# DeadOn_RTC_-_DS3234_Breakout-v11.net
KiCad netlist of a schematic drawn in EAGLE
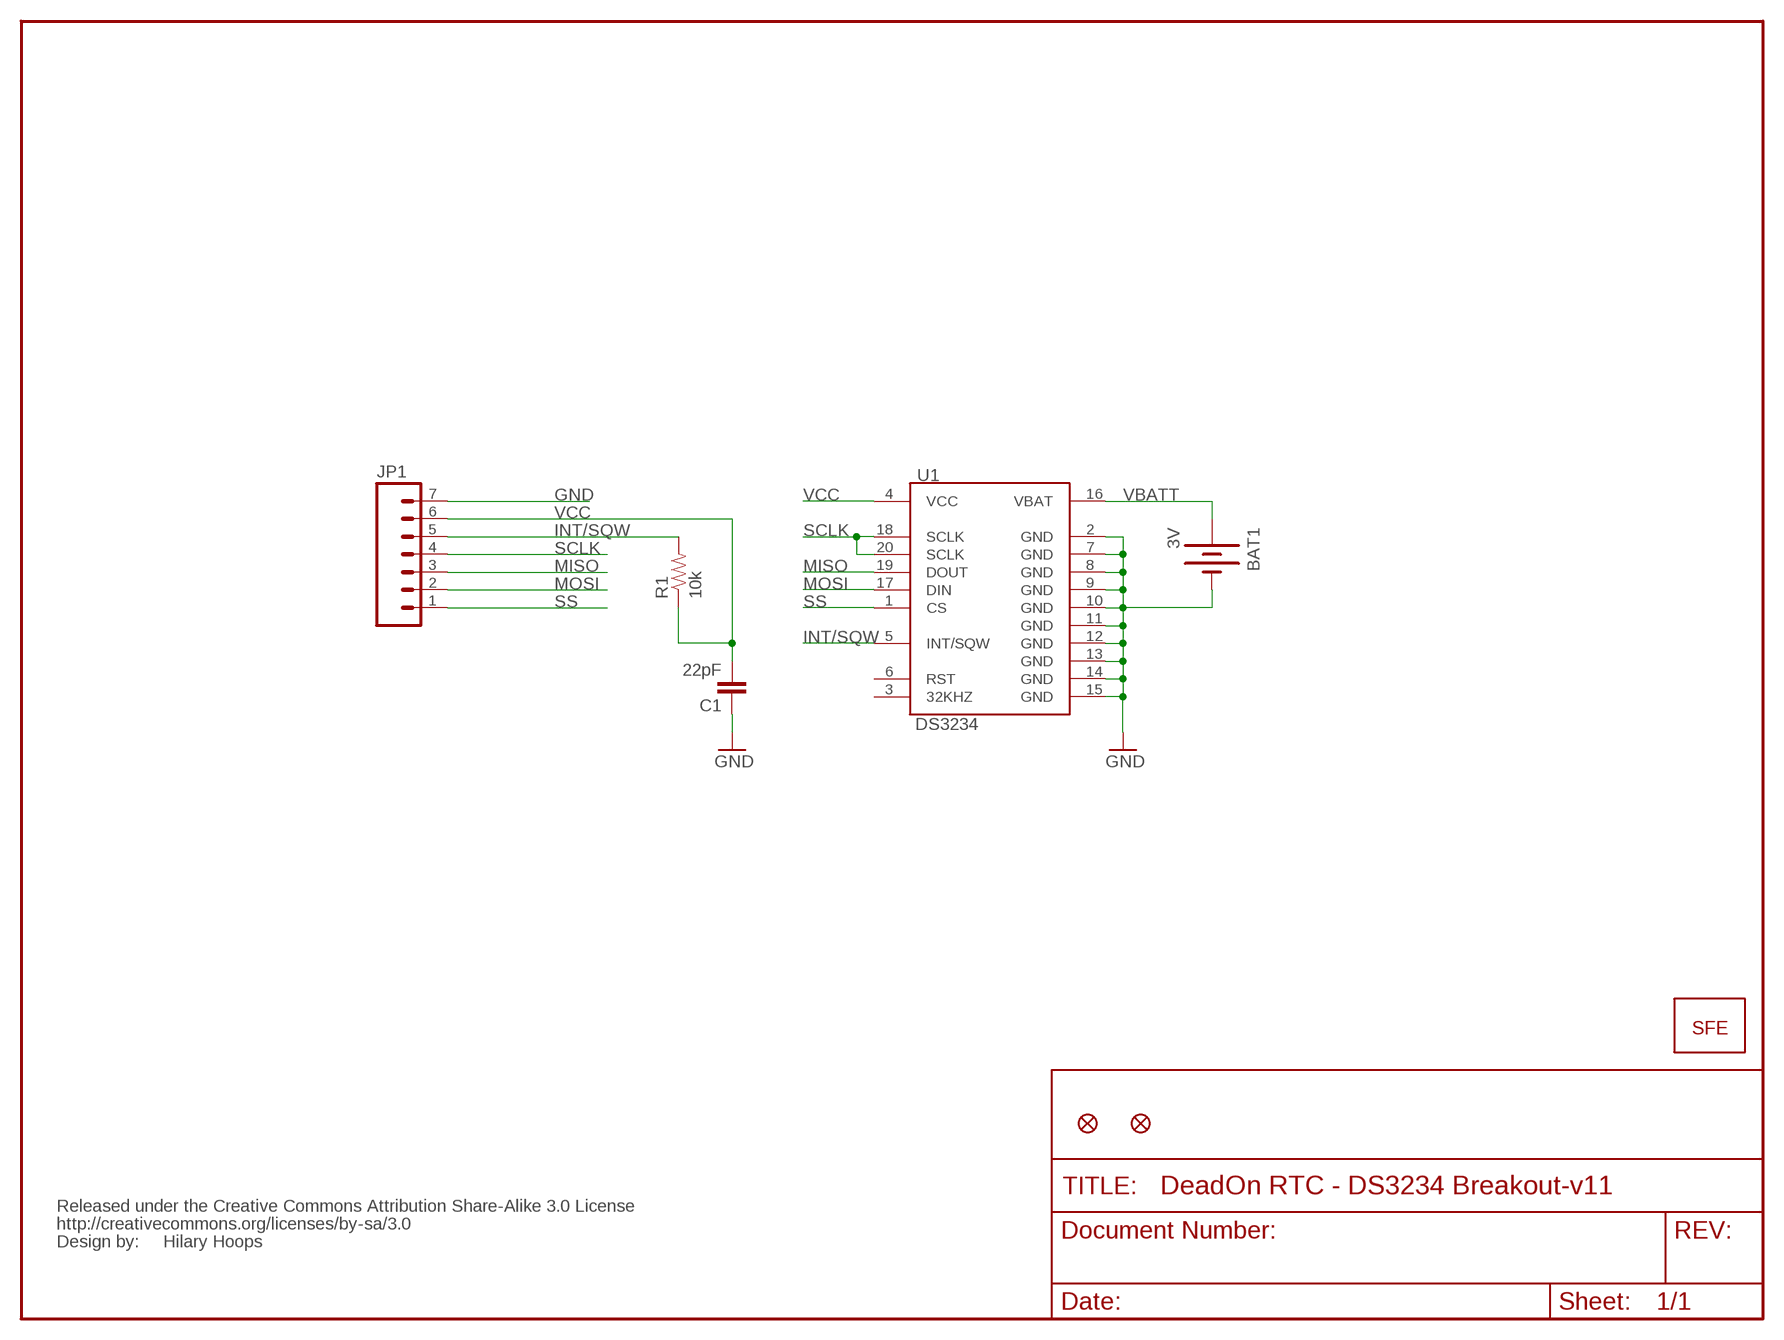
[diagram p0: schematic, sheet 1]

(export (version "E")
  (design (tool "Eeschema 10.0.6"))
  (components
    (comp (ref "BAT1")
      (value "3V")
      (footprint "eagle-import:BATTCON_12MM_CURVED")
      (libsource (lib "eagle-import") (part "BATTERY"))
    )
    (comp (ref "C1")
      (value "22pF")
      (footprint "eagle-import:0402-CAP")
      (libsource (lib "eagle-import") (part "CAP0402-CAP"))
    )
    (comp (ref "JP1")
      (value "M07")
      (footprint "eagle-import:1X07")
      (libsource (lib "eagle-import") (part "M07"))
    )
    (comp (ref "JP2")
      (value "LOGO-SFESK")
      (footprint "eagle-import:SFE-LOGO-FLAME")
      (libsource (lib "eagle-import") (part "LOGO-SFESK"))
    )
    (comp (ref "JP3")
      (value "FIDUCIAL1X2")
      (footprint "eagle-import:FIDUCIAL-1X2")
      (libsource (lib "eagle-import") (part "FIDUCIAL1X2"))
    )
    (comp (ref "JP4")
      (value "FIDUCIAL1X2")
      (footprint "eagle-import:FIDUCIAL-1X2")
      (libsource (lib "eagle-import") (part "FIDUCIAL1X2"))
    )
    (comp (ref "R1")
      (value "10k")
      (footprint "eagle-import:0402-RES")
      (libsource (lib "eagle-import") (part "RESISTOR0402-RES"))
    )
    (comp (ref "U$1")
      (value "CREATIVE_COMMONS")
      (footprint "eagle-import:CREATIVE_COMMONS")
      (libsource (lib "eagle-import") (part "CREATIVE_COMMONS"))
    )
    (comp (ref "U1")
      (value "DS3234")
      (footprint "eagle-import:DS3234")
      (libsource (lib "eagle-import") (part "DS3234"))
    )
  )
  (nets
    (net (code "1") (name "/INT{slash}SQW") (class "Default")
      (node (ref "JP1") (pin "5") (pinfunction "5_5") (pintype "passive"))
      (node (ref "R1") (pin "2") (pinfunction "2_2") (pintype "passive"))
      (node (ref "U1") (pin "5") (pinfunction "INT/SQW_5") (pintype "bidirectional"))
    )
    (net (code "2") (name "/MISO") (class "Default")
      (node (ref "JP1") (pin "3") (pinfunction "3_3") (pintype "passive"))
      (node (ref "U1") (pin "19") (pinfunction "DOUT_19") (pintype "bidirectional"))
    )
    (net (code "3") (name "/MOSI") (class "Default")
      (node (ref "JP1") (pin "2") (pinfunction "2_2") (pintype "passive"))
      (node (ref "U1") (pin "17") (pinfunction "DIN_17") (pintype "bidirectional"))
    )
    (net (code "4") (name "/SCLK") (class "Default")
      (node (ref "JP1") (pin "4") (pinfunction "4_4") (pintype "passive"))
      (node (ref "U1") (pin "18") (pinfunction "SCLK_18") (pintype "bidirectional"))
      (node (ref "U1") (pin "20") (pinfunction "SCLK_20") (pintype "bidirectional"))
    )
    (net (code "5") (name "/SS") (class "Default")
      (node (ref "JP1") (pin "1") (pinfunction "1_1") (pintype "passive"))
      (node (ref "U1") (pin "1") (pinfunction "CS_1") (pintype "bidirectional"))
    )
    (net (code "6") (name "/VBATT") (class "Default")
      (node (ref "BAT1") (pin "PWR@1") (pinfunction "+_PWR@1") (pintype "power_in"))
      (node (ref "U1") (pin "16") (pinfunction "VBAT_16") (pintype "bidirectional"))
    )
    (net (code "7") (name "/VCC") (class "Default")
      (node (ref "C1") (pin "2") (pinfunction "2_2") (pintype "passive"))
      (node (ref "JP1") (pin "6") (pinfunction "6_6") (pintype "passive"))
      (node (ref "R1") (pin "1") (pinfunction "1_1") (pintype "passive"))
      (node (ref "U1") (pin "4") (pinfunction "VCC_4") (pintype "bidirectional"))
    )
    (net (code "8") (name "GND") (class "Default")
      (node (ref "BAT1") (pin "GND") (pinfunction "-_GND") (pintype "power_in"))
      (node (ref "C1") (pin "1") (pinfunction "1_1") (pintype "passive"))
      (node (ref "JP1") (pin "7") (pinfunction "7_7") (pintype "passive"))
      (node (ref "U1") (pin "10") (pinfunction "GND_10") (pintype "bidirectional"))
      (node (ref "U1") (pin "11") (pinfunction "GND_11") (pintype "bidirectional"))
      (node (ref "U1") (pin "12") (pinfunction "GND_12") (pintype "bidirectional"))
      (node (ref "U1") (pin "13") (pinfunction "GND_13") (pintype "bidirectional"))
      (node (ref "U1") (pin "14") (pinfunction "GND_14") (pintype "bidirectional"))
      (node (ref "U1") (pin "15") (pinfunction "GND_15") (pintype "bidirectional"))
      (node (ref "U1") (pin "2") (pinfunction "GND_2") (pintype "bidirectional"))
      (node (ref "U1") (pin "7") (pinfunction "GND_7") (pintype "bidirectional"))
      (node (ref "U1") (pin "8") (pinfunction "GND_8") (pintype "bidirectional"))
      (node (ref "U1") (pin "9") (pinfunction "GND_9") (pintype "bidirectional"))
    )
    (net (code "9") (name "unconnected-(U1-32KHZ-Pad3)") (class "Default")
      (node (ref "U1") (pin "3") (pinfunction "32KHZ_3") (pintype "bidirectional"))
    )
    (net (code "10") (name "unconnected-(U1-RST-Pad6)") (class "Default")
      (node (ref "U1") (pin "6") (pinfunction "RST_6") (pintype "bidirectional"))
    )
  )
)
